# Schematic.net
KiCad netlist of a schematic drawn in Altium Designer
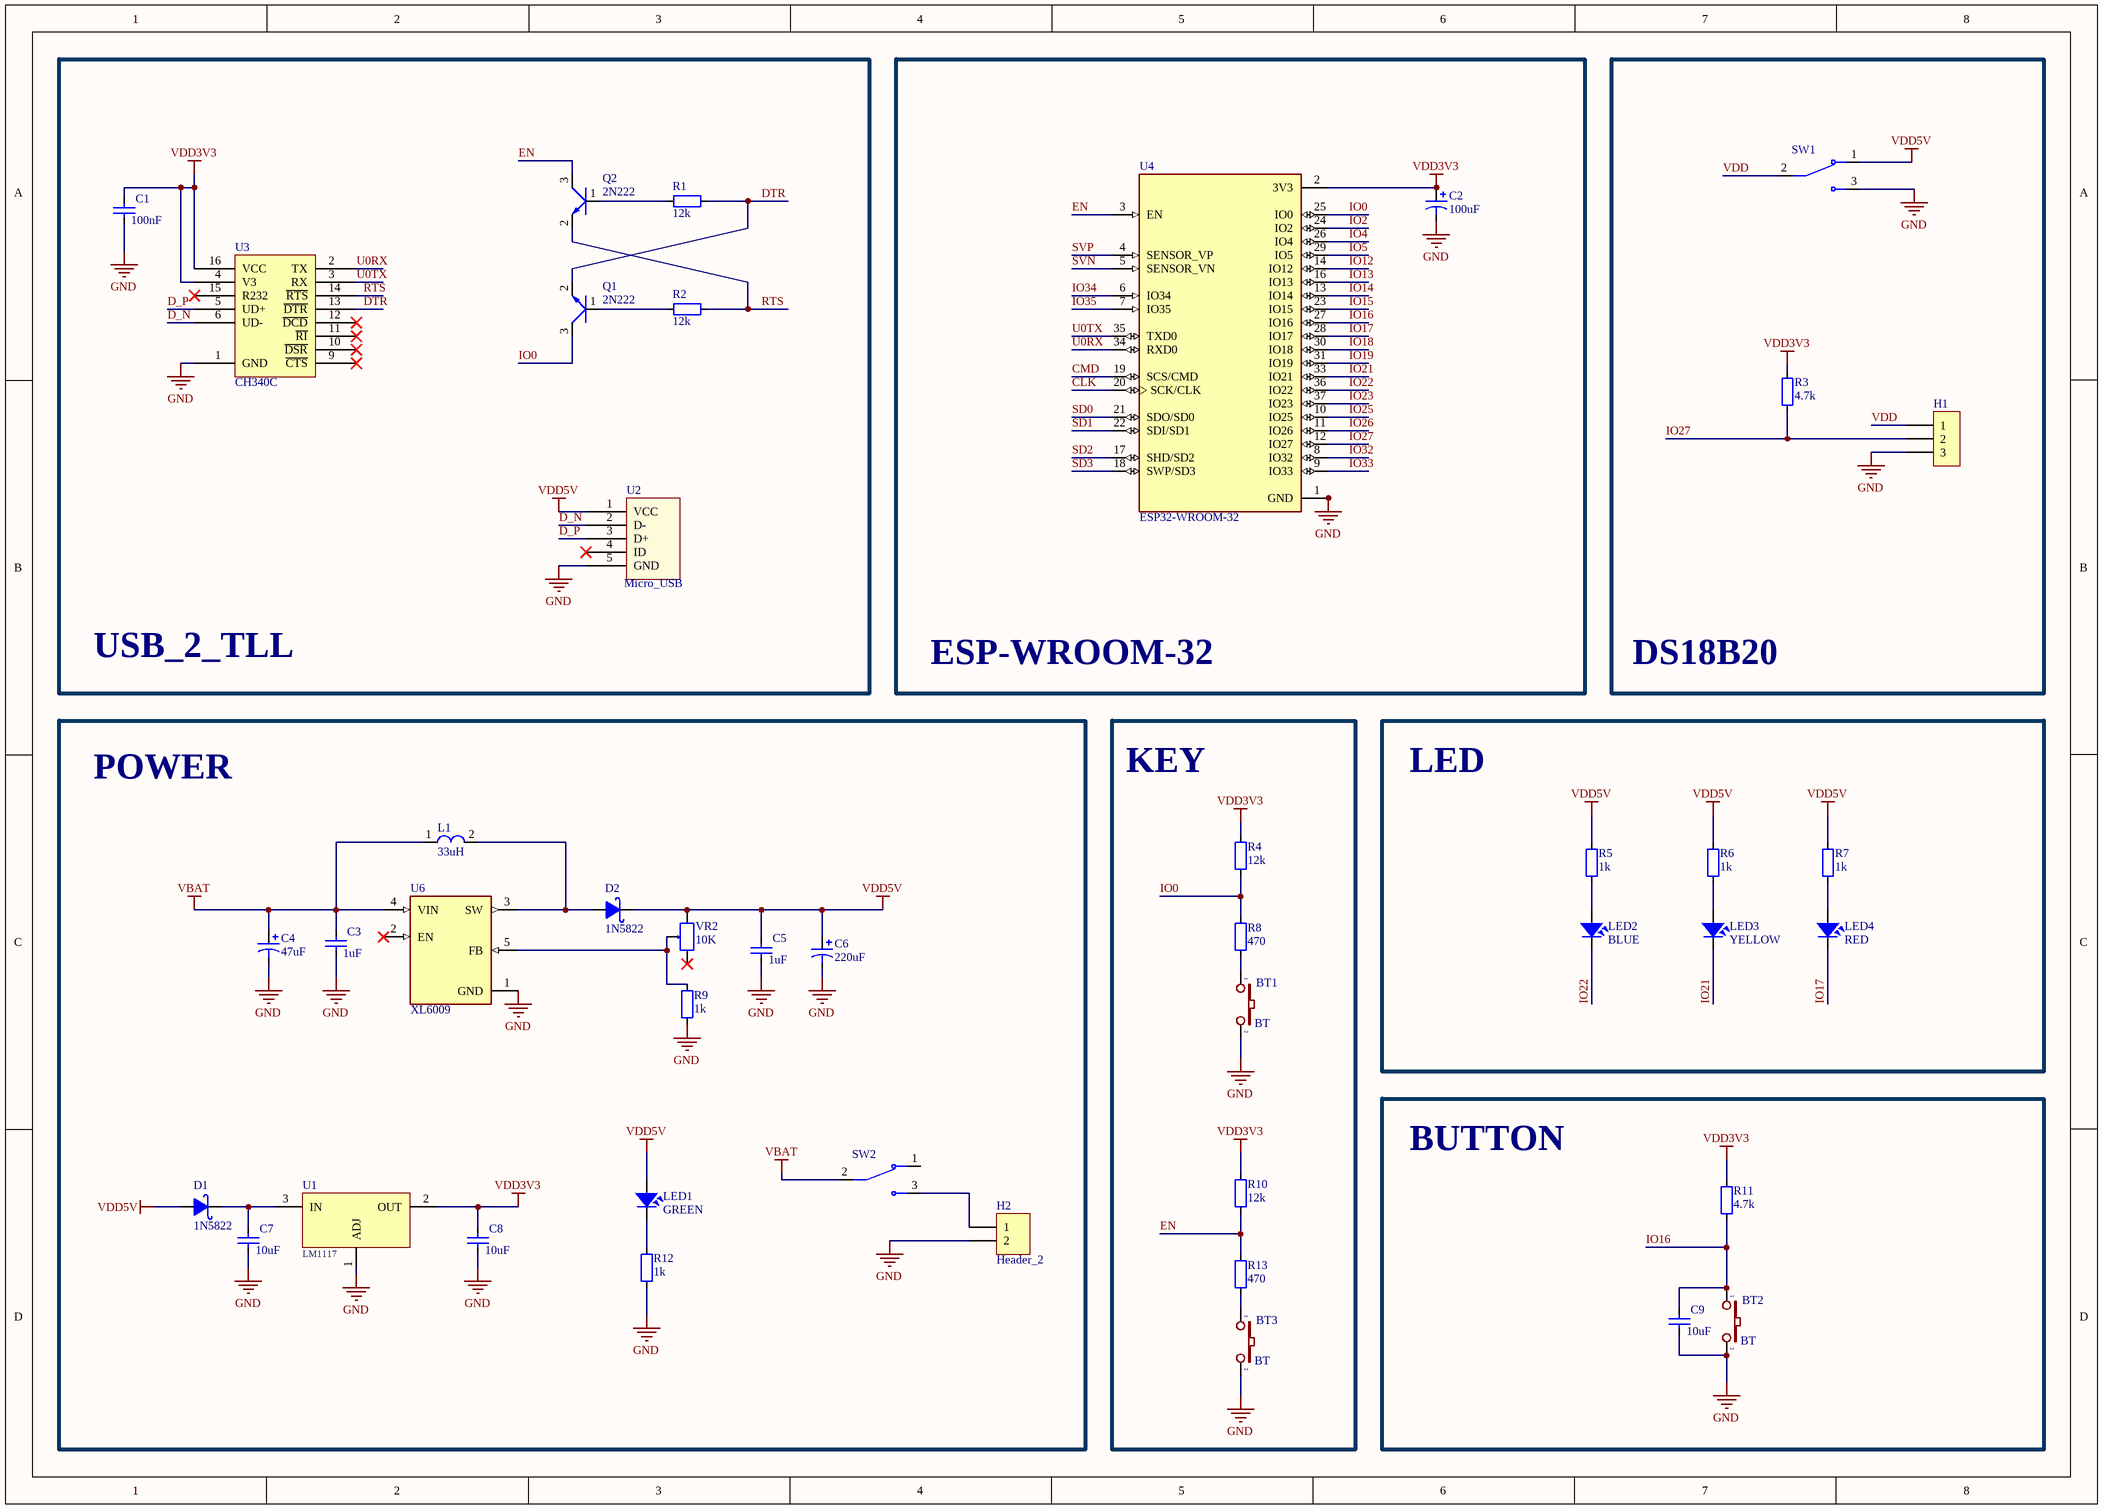
[diagram p0: Schematic.SchDoc]

(export (version "E")
  (design (tool "Eeschema 10.0.6"))
  (components
    (comp (ref "BT1")
      (value "BT")
      (footprint "BUTTON 4 PIN")
      (description "Switch button 2 pin")
      (libsource (lib "My Library") (part "SW2"))
    )
    (comp (ref "BT2")
      (value "BT")
      (footprint "BUTTON 4 PIN")
      (description "Switch button 2 pin")
      (libsource (lib "My Library") (part "SW2"))
    )
    (comp (ref "BT3")
      (value "BT")
      (footprint "BUTTON 4 PIN")
      (description "Switch button 2 pin")
      (libsource (lib "My Library") (part "SW2"))
    )
    (comp (ref "C1")
      (value "100nF")
      (footprint "CAP_0805")
      (description "Capacitor")
      (fields (field (name "PUBLISHER") "Altium Limited"))
      (libsource (lib "My Library") (part "CapSMD"))
    )
    (comp (ref "C2")
      (value "100uF")
      (footprint "C5mm")
      (description "Polarized Capacitor (Axial)")
      (fields (field (name "PUBLISHER") "Altium Limited"))
      (libsource (lib "My Library") (part "Cap Pol"))
    )
    (comp (ref "C3")
      (value "1uF")
      (footprint "CAP_0805")
      (description "Capacitor")
      (fields (field (name "PUBLISHER") "Altium Limited"))
      (libsource (lib "My Library") (part "CapSMD"))
    )
    (comp (ref "C4")
      (value "47uF")
      (footprint "C3MM")
      (description "Polarized Capacitor (Axial)")
      (fields (field (name "PUBLISHER") "Altium Limited"))
      (libsource (lib "My Library") (part "Cap Pol"))
    )
    (comp (ref "C5")
      (value "1uF")
      (footprint "CAP_0805")
      (description "Capacitor")
      (fields (field (name "PUBLISHER") "Altium Limited"))
      (libsource (lib "My Library") (part "CapSMD"))
    )
    (comp (ref "C6")
      (value "220uF")
      (footprint "C5mm")
      (description "Polarized Capacitor (Axial)")
      (fields (field (name "PUBLISHER") "Altium Limited"))
      (libsource (lib "My Library") (part "Cap Pol"))
    )
    (comp (ref "C7")
      (value "10uF")
      (footprint "CAP_0805")
      (description "Capacitor")
      (fields (field (name "PUBLISHER") "Altium Limited"))
      (libsource (lib "My Library") (part "CapSMD"))
    )
    (comp (ref "C8")
      (value "10uF")
      (footprint "CAP_0805")
      (description "Capacitor")
      (fields (field (name "PUBLISHER") "Altium Limited"))
      (libsource (lib "My Library") (part "CapSMD"))
    )
    (comp (ref "C9")
      (value "10uF")
      (footprint "CAP_0805")
      (description "Capacitor")
      (fields (field (name "PUBLISHER") "Altium Limited"))
      (libsource (lib "My Library") (part "CapSMD"))
    )
    (comp (ref "D1")
      (value "1N5822")
      (footprint "DIO-SMD-123")
      (description "Schottky Rectifiers")
      (libsource (lib "My Library") (part "1N5822"))
    )
    (comp (ref "D2")
      (value "1N5822")
      (footprint "DIO-SMD-123")
      (description "Schottky Rectifiers")
      (libsource (lib "My Library") (part "1N5822"))
    )
    (comp (ref "H1")
      (value "Header_3")
      (footprint "KF3-5.08")
      (fields
        (field (name "MANUFACTURER") "Würth Elektronik eiSos GmbH")
        (field (name "PARTNO") "691103110003")
        (field (name "CREATED BY") "Karrer Zheng")
      )
      (libsource (lib "My Library") (part "KF3"))
    )
    (comp (ref "H2")
      (value "Header_2")
      (footprint "KF2-5.08")
      (fields
        (field (name "MANUFACTURER") "Würth Elektronik eiSos GmbH")
        (field (name "PARTNO") "691103110002")
        (field (name "CREATED BY") "Karrer Zheng")
      )
      (libsource (lib "My Library") (part "KF2"))
    )
    (comp (ref "L1")
      (value "33uH")
      (footprint "L-SMD-M-7.3x4.5")
      (fields
        (field (name "PARTNO") "78477010")
        (field (name "MANUFACTURER") "Wurth Elektronik")
        (field (name "CREATED BY") "Baojun Chen")
      )
      (libsource (lib "My Library") (part "L-SMD-1"))
    )
    (comp (ref "LED1")
      (value "GREEN")
      (footprint "LED_GREEN_3MM")
      (description "LED Single colour Green and Red")
      (libsource (lib "My Library") (part "LED"))
    )
    (comp (ref "LED2")
      (value "BLUE")
      (footprint "LED_BLUE_3MM")
      (description "LED Single colour Green and Red")
      (libsource (lib "My Library") (part "LED"))
    )
    (comp (ref "LED3")
      (value "YELLOW")
      (footprint "LED_YELLOW_3MM")
      (description "LED Single colour Green and Red")
      (libsource (lib "My Library") (part "LED"))
    )
    (comp (ref "LED4")
      (value "RED")
      (footprint "LED_RED_3MM")
      (description "LED Single colour Green and Red")
      (libsource (lib "My Library") (part "LED"))
    )
    (comp (ref "Q1")
      (value "2N222")
      (footprint "SOT23D")
      (description "NPN 600mW, ECB")
      (libsource (lib "My Library") (part "2N222"))
    )
    (comp (ref "Q2")
      (value "2N222")
      (footprint "SOT23D")
      (description "NPN 600mW, ECB")
      (libsource (lib "My Library") (part "2N222"))
    )
    (comp (ref "R1")
      (value "12k")
      (footprint "RES-SMD-0805")
      (description "Resistor")
      (fields
        (field (name "MANUFACTURER") "Generic Components")
        (field (name "PUBLISHER") "Altium Hobart Technology Centre")
      )
      (libsource (lib "My Library") (part "Resistor - SMD"))
    )
    (comp (ref "R2")
      (value "12k")
      (footprint "RES-SMD-0805")
      (description "Resistor")
      (fields
        (field (name "MANUFACTURER") "Generic Components")
        (field (name "PUBLISHER") "Altium Hobart Technology Centre")
      )
      (libsource (lib "My Library") (part "Resistor - SMD"))
    )
    (comp (ref "R3")
      (value "4.7k")
      (footprint "RES-SMD-0805")
      (description "Resistor")
      (fields
        (field (name "MANUFACTURER") "Generic Components")
        (field (name "PUBLISHER") "Altium Hobart Technology Centre")
      )
      (libsource (lib "My Library") (part "Resistor - SMD"))
    )
    (comp (ref "R4")
      (value "12k")
      (footprint "RES-SMD-0805")
      (description "Resistor")
      (fields
        (field (name "MANUFACTURER") "Generic Components")
        (field (name "PUBLISHER") "Altium Hobart Technology Centre")
      )
      (libsource (lib "My Library") (part "Resistor - SMD"))
    )
    (comp (ref "R5")
      (value "1k")
      (footprint "RES-SMD-0805")
      (description "Resistor")
      (fields
        (field (name "MANUFACTURER") "Generic Components")
        (field (name "PUBLISHER") "Altium Hobart Technology Centre")
      )
      (libsource (lib "My Library") (part "Resistor - SMD"))
    )
    (comp (ref "R6")
      (value "1k")
      (footprint "RES-SMD-0805")
      (description "Resistor")
      (fields
        (field (name "MANUFACTURER") "Generic Components")
        (field (name "PUBLISHER") "Altium Hobart Technology Centre")
      )
      (libsource (lib "My Library") (part "Resistor - SMD"))
    )
    (comp (ref "R7")
      (value "1k")
      (footprint "RES-SMD-0805")
      (description "Resistor")
      (fields
        (field (name "MANUFACTURER") "Generic Components")
        (field (name "PUBLISHER") "Altium Hobart Technology Centre")
      )
      (libsource (lib "My Library") (part "Resistor - SMD"))
    )
    (comp (ref "R8")
      (value "470")
      (footprint "RES-SMD-0805")
      (description "Resistor")
      (fields
        (field (name "MANUFACTURER") "Generic Components")
        (field (name "PUBLISHER") "Altium Hobart Technology Centre")
      )
      (libsource (lib "My Library") (part "Resistor - SMD"))
    )
    (comp (ref "R9")
      (value "1k")
      (footprint "RES-SMD-0805")
      (description "Resistor")
      (fields
        (field (name "MANUFACTURER") "Generic Components")
        (field (name "PUBLISHER") "Altium Hobart Technology Centre")
      )
      (libsource (lib "My Library") (part "Resistor - SMD"))
    )
    (comp (ref "R10")
      (value "12k")
      (footprint "RES-SMD-0805")
      (description "Resistor")
      (fields
        (field (name "MANUFACTURER") "Generic Components")
        (field (name "PUBLISHER") "Altium Hobart Technology Centre")
      )
      (libsource (lib "My Library") (part "Resistor - SMD"))
    )
    (comp (ref "R11")
      (value "4.7k")
      (footprint "RES-SMD-0805")
      (description "Resistor")
      (fields
        (field (name "MANUFACTURER") "Generic Components")
        (field (name "PUBLISHER") "Altium Hobart Technology Centre")
      )
      (libsource (lib "My Library") (part "Resistor - SMD"))
    )
    (comp (ref "R12")
      (value "1k")
      (footprint "RES-SMD-0805")
      (description "Resistor")
      (fields
        (field (name "MANUFACTURER") "Generic Components")
        (field (name "PUBLISHER") "Altium Hobart Technology Centre")
      )
      (libsource (lib "My Library") (part "Resistor - SMD"))
    )
    (comp (ref "R13")
      (value "470")
      (footprint "RES-SMD-0805")
      (description "Resistor")
      (fields
        (field (name "MANUFACTURER") "Generic Components")
        (field (name "PUBLISHER") "Altium Hobart Technology Centre")
      )
      (libsource (lib "My Library") (part "Resistor - SMD"))
    )
    (comp (ref "SW1")
      (value "500SSP1S2M2QEA")
      (footprint "3pin")
      (description "Slide Switch SPDT Through Hole")
      (libsource (lib "500SSP1S2M2QEA") (part "500SSP1S2M2QEA"))
    )
    (comp (ref "SW2")
      (value "500SSP1S2M2QEA")
      (footprint "3pin")
      (description "Slide Switch SPDT Through Hole")
      (libsource (lib "500SSP1S2M2QEA") (part "500SSP1S2M2QEA"))
    )
    (comp (ref "U1")
      (value "LM1117")
      (footprint "LM1117-SOP")
      (description "800mA Low-Dropout Linear Regulator")
      (fields (field (name "CREATOR") "Nguyen Ba Bien"))
      (libsource (lib "My Library") (part "LM1117-ADJ"))
    )
    (comp (ref "U2")
      (value "Micro_USB")
      (footprint "AMPHENOL_10118194-0001LF")
      (libsource (lib "Micro_USB") (part "Micro_USB"))
    )
    (comp (ref "U3")
      (value "CH340C")
      (footprint "SO016")
      (description "USB to serial chip CH340")
      (fields (field (name "MF") "WCH"))
      (libsource (lib "My Library") (part "CH340C"))
    )
    (comp (ref "U4")
      (value "ESP32-WROOM-32")
      (footprint "MODULE_ESP32-WROOM-32")
      (description "Bluetooth, WiFi Transceiver Module 2.4GHz ~ 2.5GHz Surface Mount")
      (fields (field (name "MF") "Espressif Systems") (field (name "DIGI-KEY_PART_NUMBER") "1904-1010-1-ND"))
      (libsource (lib "My Library") (part "ESP32-WROOM-32"))
    )
    (comp (ref "U6")
      (value "XL6009")
      (footprint "DPAK170P1435X465-6N")
      (libsource (lib "XL6009") (part "XL6009"))
    )
    (comp (ref "VR2")
      (value "10K")
      (footprint "VR")
      (description "Var Resistor")
      (libsource (lib "My Library") (part "VR"))
    )
  )
  (nets
    (net (code "1") (name "/CLK") (class "Default")
      (node (ref "U4") (pin "20") (pinfunction "SCK/CLK_20") (pintype "bidirectional"))
    )
    (net (code "2") (name "/CMD") (class "Default")
      (node (ref "U4") (pin "19") (pinfunction "SCS/CMD_19") (pintype "bidirectional"))
    )
    (net (code "3") (name "/DTR") (class "Default")
      (node (ref "Q1") (pin "2") (pinfunction "E_2") (pintype "passive"))
      (node (ref "R1") (pin "2") (pinfunction "2_2") (pintype "passive"))
      (node (ref "U3") (pin "13") (pinfunction "~{DTR}_13") (pintype "passive"))
    )
    (net (code "4") (name "/D_N") (class "Default")
      (node (ref "U2") (pin "2") (pinfunction "D-_2") (pintype "passive"))
      (node (ref "U3") (pin "6") (pinfunction "UD-_6") (pintype "passive"))
    )
    (net (code "5") (name "/D_P") (class "Default")
      (node (ref "U2") (pin "3") (pinfunction "D+_3") (pintype "passive"))
      (node (ref "U3") (pin "5") (pinfunction "UD+_5") (pintype "passive"))
    )
    (net (code "6") (name "/EN") (class "Default")
      (node (ref "Q2") (pin "3") (pinfunction "C_3") (pintype "passive"))
      (node (ref "R10") (pin "1") (pinfunction "1_1") (pintype "passive"))
      (node (ref "R13") (pin "2") (pinfunction "2_2") (pintype "passive"))
      (node (ref "U4") (pin "3") (pinfunction "EN_3") (pintype "input"))
    )
    (net (code "7") (name "/IO0") (class "Default")
      (node (ref "Q1") (pin "3") (pinfunction "C_3") (pintype "passive"))
      (node (ref "R4") (pin "1") (pinfunction "1_1") (pintype "passive"))
      (node (ref "R8") (pin "2") (pinfunction "2_2") (pintype "passive"))
      (node (ref "U4") (pin "25") (pinfunction "IO0_25") (pintype "bidirectional"))
    )
    (net (code "8") (name "/IO2") (class "Default")
      (node (ref "U4") (pin "24") (pinfunction "IO2_24") (pintype "bidirectional"))
    )
    (net (code "9") (name "/IO4") (class "Default")
      (node (ref "U4") (pin "26") (pinfunction "IO4_26") (pintype "bidirectional"))
    )
    (net (code "10") (name "/IO5") (class "Default")
      (node (ref "U4") (pin "29") (pinfunction "IO5_29") (pintype "bidirectional"))
    )
    (net (code "11") (name "/IO12") (class "Default")
      (node (ref "U4") (pin "14") (pinfunction "IO12_14") (pintype "bidirectional"))
    )
    (net (code "12") (name "/IO13") (class "Default")
      (node (ref "U4") (pin "16") (pinfunction "IO13_16") (pintype "bidirectional"))
    )
    (net (code "13") (name "/IO14") (class "Default")
      (node (ref "U4") (pin "13") (pinfunction "IO14_13") (pintype "bidirectional"))
    )
    (net (code "14") (name "/IO15") (class "Default")
      (node (ref "U4") (pin "23") (pinfunction "IO15_23") (pintype "bidirectional"))
    )
    (net (code "15") (name "/IO16") (class "Default")
      (node (ref "BT2") (pin "1") (pinfunction "1_1") (pintype "passive"))
      (node (ref "C9") (pin "2") (pinfunction "2_2") (pintype "passive"))
      (node (ref "R11") (pin "1") (pinfunction "1_1") (pintype "passive"))
      (node (ref "U4") (pin "27") (pinfunction "IO16_27") (pintype "bidirectional"))
    )
    (net (code "16") (name "/IO17") (class "Default")
      (node (ref "LED4") (pin "2") (pinfunction "2_2") (pintype "passive"))
      (node (ref "U4") (pin "28") (pinfunction "IO17_28") (pintype "bidirectional"))
    )
    (net (code "17") (name "/IO18") (class "Default")
      (node (ref "U4") (pin "30") (pinfunction "IO18_30") (pintype "bidirectional"))
    )
    (net (code "18") (name "/IO19") (class "Default")
      (node (ref "U4") (pin "31") (pinfunction "IO19_31") (pintype "bidirectional"))
    )
    (net (code "19") (name "/IO21") (class "Default")
      (node (ref "LED3") (pin "2") (pinfunction "2_2") (pintype "passive"))
      (node (ref "U4") (pin "33") (pinfunction "IO21_33") (pintype "bidirectional"))
    )
    (net (code "20") (name "/IO22") (class "Default")
      (node (ref "LED2") (pin "2") (pinfunction "2_2") (pintype "passive"))
      (node (ref "U4") (pin "36") (pinfunction "IO22_36") (pintype "bidirectional"))
    )
    (net (code "21") (name "/IO23") (class "Default")
      (node (ref "U4") (pin "37") (pinfunction "IO23_37") (pintype "bidirectional"))
    )
    (net (code "22") (name "/IO25") (class "Default")
      (node (ref "U4") (pin "10") (pinfunction "IO25_10") (pintype "bidirectional"))
    )
    (net (code "23") (name "/IO26") (class "Default")
      (node (ref "U4") (pin "11") (pinfunction "IO26_11") (pintype "bidirectional"))
    )
    (net (code "24") (name "/IO27") (class "Default")
      (node (ref "H1") (pin "2") (pinfunction "2_2") (pintype "passive"))
      (node (ref "R3") (pin "1") (pinfunction "1_1") (pintype "passive"))
      (node (ref "U4") (pin "12") (pinfunction "IO27_12") (pintype "bidirectional"))
    )
    (net (code "25") (name "/IO32") (class "Default")
      (node (ref "U4") (pin "8") (pinfunction "IO32_8") (pintype "bidirectional"))
    )
    (net (code "26") (name "/IO33") (class "Default")
      (node (ref "U4") (pin "9") (pinfunction "IO33_9") (pintype "bidirectional"))
    )
    (net (code "27") (name "/IO34") (class "Default")
      (node (ref "U4") (pin "6") (pinfunction "IO34_6") (pintype "input"))
    )
    (net (code "28") (name "/IO35") (class "Default")
      (node (ref "U4") (pin "7") (pinfunction "IO35_7") (pintype "input"))
    )
    (net (code "29") (name "/RTS") (class "Default")
      (node (ref "Q2") (pin "2") (pinfunction "E_2") (pintype "passive"))
      (node (ref "R2") (pin "2") (pinfunction "2_2") (pintype "passive"))
      (node (ref "U3") (pin "14") (pinfunction "~{RTS}_14") (pintype "passive"))
    )
    (net (code "30") (name "/SD0") (class "Default")
      (node (ref "U4") (pin "21") (pinfunction "SDO/SD0_21") (pintype "bidirectional"))
    )
    (net (code "31") (name "/SD1") (class "Default")
      (node (ref "U4") (pin "22") (pinfunction "SDI/SD1_22") (pintype "bidirectional"))
    )
    (net (code "32") (name "/SD2") (class "Default")
      (node (ref "U4") (pin "17") (pinfunction "SHD/SD2_17") (pintype "bidirectional"))
    )
    (net (code "33") (name "/SD3") (class "Default")
      (node (ref "U4") (pin "18") (pinfunction "SWP/SD3_18") (pintype "bidirectional"))
    )
    (net (code "34") (name "/SVN") (class "Default")
      (node (ref "U4") (pin "5") (pinfunction "SENSOR_VN_5") (pintype "input"))
    )
    (net (code "35") (name "/SVP") (class "Default")
      (node (ref "U4") (pin "4") (pinfunction "SENSOR_VP_4") (pintype "input"))
    )
    (net (code "36") (name "/U0RX") (class "Default")
      (node (ref "U3") (pin "2") (pinfunction "TX_2") (pintype "passive"))
      (node (ref "U4") (pin "34") (pinfunction "RXD0_34") (pintype "bidirectional"))
    )
    (net (code "37") (name "/U0TX") (class "Default")
      (node (ref "U3") (pin "3") (pinfunction "RX_3") (pintype "passive"))
      (node (ref "U4") (pin "35") (pinfunction "TXD0_35") (pintype "bidirectional"))
    )
    (net (code "38") (name "/VDD") (class "Default")
      (node (ref "H1") (pin "1") (pinfunction "1_1") (pintype "passive"))
      (node (ref "SW1") (pin "2") (pinfunction "COM_2") (pintype "passive"))
    )
    (net (code "39") (name "GND") (class "Default")
      (node (ref "BT1") (pin "2") (pinfunction "2_2") (pintype "passive"))
      (node (ref "BT2") (pin "2") (pinfunction "2_2") (pintype "passive"))
      (node (ref "BT3") (pin "2") (pinfunction "2_2") (pintype "passive"))
      (node (ref "C1") (pin "1") (pinfunction "1_1") (pintype "passive"))
      (node (ref "C2") (pin "2") (pinfunction "2_2") (pintype "passive"))
      (node (ref "C3") (pin "1") (pinfunction "1_1") (pintype "passive"))
      (node (ref "C4") (pin "2") (pinfunction "2_2") (pintype "passive"))
      (node (ref "C5") (pin "1") (pinfunction "1_1") (pintype "passive"))
      (node (ref "C6") (pin "2") (pinfunction "2_2") (pintype "passive"))
      (node (ref "C7") (pin "1") (pinfunction "1_1") (pintype "passive"))
      (node (ref "C8") (pin "1") (pinfunction "1_1") (pintype "passive"))
      (node (ref "C9") (pin "1") (pinfunction "1_1") (pintype "passive"))
      (node (ref "H1") (pin "3") (pinfunction "3_3") (pintype "passive"))
      (node (ref "H2") (pin "2") (pinfunction "2_2") (pintype "passive"))
      (node (ref "R12") (pin "1") (pinfunction "1_1") (pintype "passive"))
      (node (ref "R9") (pin "1") (pinfunction "1_1") (pintype "passive"))
      (node (ref "SW1") (pin "3") (pinfunction "NO_3") (pintype "passive"))
      (node (ref "U1") (pin "1") (pinfunction "ADJ_1") (pintype "passive"))
      (node (ref "U2") (pin "5") (pinfunction "GND_5") (pintype "passive"))
      (node (ref "U3") (pin "1") (pinfunction "GND_1") (pintype "passive"))
      (node (ref "U4") (pin "1") (pinfunction "GND_1") (pintype "power_in"))
      (node (ref "U4") (pin "15") (pinfunction "GND_15") (pintype "power_in"))
      (node (ref "U4") (pin "38") (pinfunction "GND_38") (pintype "power_in"))
      (node (ref "U4") (pin "39_1") (pinfunction "GND_39_1") (pintype "power_in"))
      (node (ref "U4") (pin "39_10") (pinfunction "GND_39_10") (pintype "power_in"))
      (node (ref "U4") (pin "39_11") (pinfunction "GND_39_11") (pintype "power_in"))
      (node (ref "U4") (pin "39_12") (pinfunction "GND_39_12") (pintype "power_in"))
      (node (ref "U4") (pin "39_13") (pinfunction "GND_39_13") (pintype "power_in"))
      (node (ref "U4") (pin "39_14") (pinfunction "GND_39_14") (pintype "power_in"))
      (node (ref "U4") (pin "39_15") (pinfunction "GND_39_15") (pintype "power_in"))
      (node (ref "U4") (pin "39_16") (pinfunction "GND_39_16") (pintype "power_in"))
      (node (ref "U4") (pin "39_17") (pinfunction "GND_39_17") (pintype "power_in"))
      (node (ref "U4") (pin "39_18") (pinfunction "GND_39_18") (pintype "power_in"))
      (node (ref "U4") (pin "39_19") (pinfunction "GND_39_19") (pintype "power_in"))
      (node (ref "U4") (pin "39_2") (pinfunction "GND_39_2") (pintype "power_in"))
      (node (ref "U4") (pin "39_20") (pinfunction "GND_39_20") (pintype "power_in"))
      (node (ref "U4") (pin "39_21") (pinfunction "GND_39_21") (pintype "power_in"))
      (node (ref "U4") (pin "39_3") (pinfunction "GND_39_3") (pintype "power_in"))
      (node (ref "U4") (pin "39_4") (pinfunction "GND_39_4") (pintype "power_in"))
      (node (ref "U4") (pin "39_5") (pinfunction "GND_39_5") (pintype "power_in"))
      (node (ref "U4") (pin "39_6") (pinfunction "GND_39_6") (pintype "power_in"))
      (node (ref "U4") (pin "39_7") (pinfunction "GND_39_7") (pintype "power_in"))
      (node (ref "U4") (pin "39_8") (pinfunction "GND_39_8") (pintype "power_in"))
      (node (ref "U4") (pin "39_9") (pinfunction "GND_39_9") (pintype "power_in"))
      (node (ref "U6") (pin "1") (pinfunction "GND_1") (pintype "power_in"))
    )
    (net (code "40") (name "Net-(BT1-Pad1)") (class "Default")
      (node (ref "BT1") (pin "1") (pinfunction "1_1") (pintype "passive"))
      (node (ref "R8") (pin "1") (pinfunction "1_1") (pintype "passive"))
    )
    (net (code "41") (name "Net-(BT3-Pad1)") (class "Default")
      (node (ref "BT3") (pin "1") (pinfunction "1_1") (pintype "passive"))
      (node (ref "R13") (pin "1") (pinfunction "1_1") (pintype "passive"))
    )
    (net (code "42") (name "Net-(D1-K)") (class "Default")
      (node (ref "C7") (pin "2") (pinfunction "2_2") (pintype "passive"))
      (node (ref "D1") (pin "2") (pinfunction "K_2") (pintype "passive"))
      (node (ref "U1") (pin "3") (pinfunction "IN_3") (pintype "passive"))
    )
    (net (code "43") (name "Net-(D2-A)") (class "Default")
      (node (ref "D2") (pin "1") (pinfunction "A_1") (pintype "passive"))
      (node (ref "L1") (pin "2") (pinfunction "2_2") (pintype "passive"))
      (node (ref "U6") (pin "3") (pinfunction "SW_3") (pintype "output"))
    )
    (net (code "44") (name "Net-(LED1-Pad2)") (class "Default")
      (node (ref "LED1") (pin "2") (pinfunction "2_2") (pintype "passive"))
      (node (ref "R12") (pin "2") (pinfunction "2_2") (pintype "passive"))
    )
    (net (code "45") (name "Net-(LED2-Pad1)") (class "Default")
      (node (ref "LED2") (pin "1") (pinfunction "1_1") (pintype "passive"))
      (node (ref "R5") (pin "1") (pinfunction "1_1") (pintype "passive"))
    )
    (net (code "46") (name "Net-(LED3-Pad1)") (class "Default")
      (node (ref "LED3") (pin "1") (pinfunction "1_1") (pintype "passive"))
      (node (ref "R6") (pin "1") (pinfunction "1_1") (pintype "passive"))
    )
    (net (code "47") (name "Net-(LED4-Pad1)") (class "Default")
      (node (ref "LED4") (pin "1") (pinfunction "1_1") (pintype "passive"))
      (node (ref "R7") (pin "1") (pinfunction "1_1") (pintype "passive"))
    )
    (net (code "48") (name "Net-(Q1-B)") (class "Default")
      (node (ref "Q1") (pin "1") (pinfunction "B_1") (pintype "passive"))
      (node (ref "R2") (pin "1") (pinfunction "1_1") (pintype "passive"))
    )
    (net (code "49") (name "Net-(Q2-B)") (class "Default")
      (node (ref "Q2") (pin "1") (pinfunction "B_1") (pintype "passive"))
      (node (ref "R1") (pin "1") (pinfunction "1_1") (pintype "passive"))
    )
    (net (code "50") (name "Net-(SW2-NO)") (class "Default")
      (node (ref "H2") (pin "1") (pinfunction "1_1") (pintype "passive"))
      (node (ref "SW2") (pin "3") (pinfunction "NO_3") (pintype "passive"))
    )
    (net (code "51") (name "Net-(U6-FB)") (class "Default")
      (node (ref "R9") (pin "2") (pinfunction "2_2") (pintype "passive"))
      (node (ref "U6") (pin "5") (pinfunction "FB_5") (pintype "input"))
      (node (ref "VR2") (pin "2") (pinfunction "2_2") (pintype "passive"))
    )
    (net (code "52") (name "VBAT") (class "Default")
      (node (ref "C3") (pin "2") (pinfunction "2_2") (pintype "passive"))
      (node (ref "C4") (pin "1") (pinfunction "1_1") (pintype "passive"))
      (node (ref "L1") (pin "1") (pinfunction "1_1") (pintype "passive"))
      (node (ref "SW2") (pin "2") (pinfunction "COM_2") (pintype "passive"))
      (node (ref "U6") (pin "4") (pinfunction "VIN_4") (pintype "input"))
    )
    (net (code "53") (name "VDD3V3") (class "Default")
      (node (ref "C1") (pin "2") (pinfunction "2_2") (pintype "passive"))
      (node (ref "C2") (pin "1") (pinfunction "1_1") (pintype "passive"))
      (node (ref "C8") (pin "2") (pinfunction "2_2") (pintype "passive"))
      (node (ref "R10") (pin "2") (pinfunction "2_2") (pintype "passive"))
      (node (ref "R11") (pin "2") (pinfunction "2_2") (pintype "passive"))
      (node (ref "R3") (pin "2") (pinfunction "2_2") (pintype "passive"))
      (node (ref "R4") (pin "2") (pinfunction "2_2") (pintype "passive"))
      (node (ref "U1") (pin "2") (pinfunction "OUT_2") (pintype "passive"))
      (node (ref "U3") (pin "16") (pinfunction "VCC_16") (pintype "passive"))
      (node (ref "U3") (pin "4") (pinfunction "V3_4") (pintype "passive"))
      (node (ref "U4") (pin "2") (pinfunction "3V3_2") (pintype "power_in"))
    )
    (net (code "54") (name "VDD5V") (class "Default")
      (node (ref "C5") (pin "2") (pinfunction "2_2") (pintype "passive"))
      (node (ref "C6") (pin "1") (pinfunction "1_1") (pintype "passive"))
      (node (ref "D1") (pin "1") (pinfunction "A_1") (pintype "passive"))
      (node (ref "D2") (pin "2") (pinfunction "K_2") (pintype "passive"))
      (node (ref "LED1") (pin "1") (pinfunction "1_1") (pintype "passive"))
      (node (ref "R5") (pin "2") (pinfunction "2_2") (pintype "passive"))
      (node (ref "R6") (pin "2") (pinfunction "2_2") (pintype "passive"))
      (node (ref "R7") (pin "2") (pinfunction "2_2") (pintype "passive"))
      (node (ref "SW1") (pin "1") (pinfunction "NC_1") (pintype "passive"))
      (node (ref "U2") (pin "1") (pinfunction "VCC_1") (pintype "passive"))
      (node (ref "VR2") (pin "3") (pinfunction "3_3") (pintype "passive"))
    )
    (net (code "55") (name "unconnected-(SW2-NC-Pad1)") (class "Default")
      (node (ref "SW2") (pin "1") (pinfunction "NC_1") (pintype "passive"))
    )
    (net (code "56") (name "unconnected-(U2-ID-Pad4)") (class "Default")
      (node (ref "U2") (pin "4") (pinfunction "ID_4") (pintype "passive+no_connect"))
    )
    (net (code "57") (name "unconnected-(U3-R232-Pad15)") (class "Default")
      (node (ref "U3") (pin "15") (pinfunction "R232_15") (pintype "passive+no_connect"))
    )
    (net (code "58") (name "unconnected-(U3-~{CTS}-Pad9)") (class "Default")
      (node (ref "U3") (pin "9") (pinfunction "~{CTS}_9") (pintype "passive+no_connect"))
    )
    (net (code "59") (name "unconnected-(U3-~{DCD}-Pad12)") (class "Default")
      (node (ref "U3") (pin "12") (pinfunction "~{DCD}_12") (pintype "passive+no_connect"))
    )
    (net (code "60") (name "unconnected-(U3-~{DSR}-Pad10)") (class "Default")
      (node (ref "U3") (pin "10") (pinfunction "~{DSR}_10") (pintype "passive+no_connect"))
    )
    (net (code "61") (name "unconnected-(U3-~{RI}-Pad11)") (class "Default")
      (node (ref "U3") (pin "11") (pinfunction "~{RI}_11") (pintype "passive+no_connect"))
    )
    (net (code "62") (name "unconnected-(U6-EN-Pad2)") (class "Default")
      (node (ref "U6") (pin "2") (pinfunction "EN_2") (pintype "input+no_connect"))
    )
    (net (code "63") (name "unconnected-(VR2-Pad1)") (class "Default")
      (node (ref "VR2") (pin "1") (pinfunction "1_1") (pintype "passive+no_connect"))
    )
  )
)
